# micro.net
KiCad netlist of a schematic drawn in Altium Designer
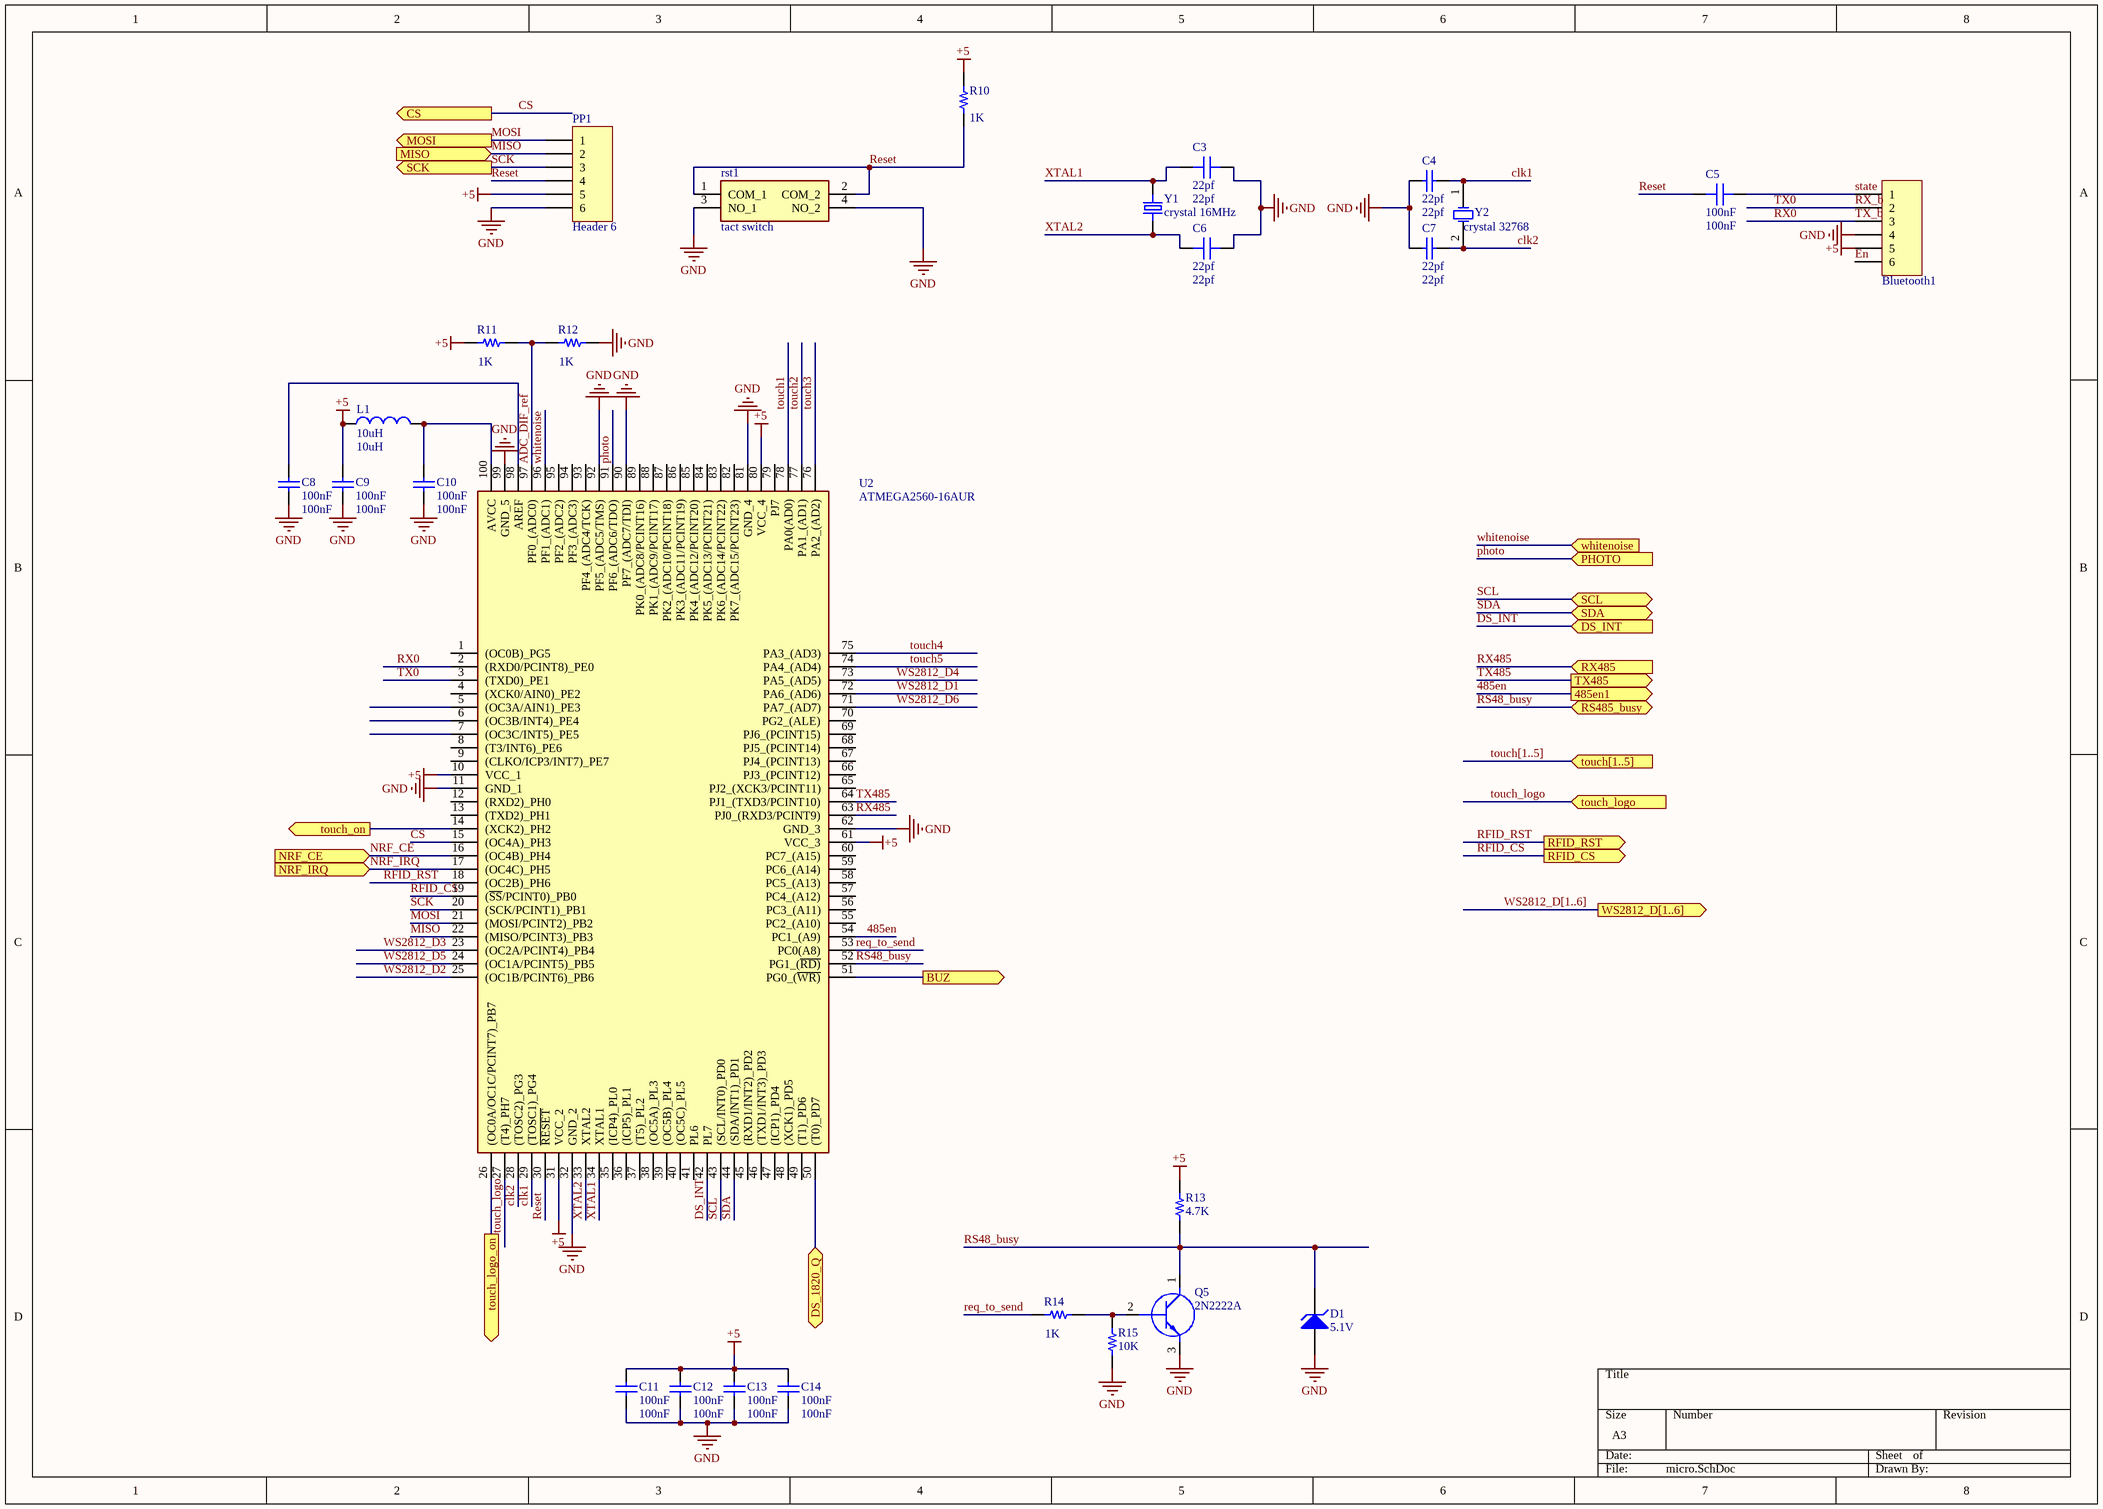
[diagram p0: micro.SchDoc]

(export (version "E")
  (design (tool "Eeschema 10.0.6"))
  (components
    (comp (ref "Bluetooth1")
      (value "Header 6")
      (footprint "H-1x6")
      (description "Header, 6-Pin , female")
      (libsource (lib "Mine-Discreet") (part "H-1x6"))
    )
    (comp (ref "C3")
      (value "22pf")
      (footprint "0603C")
      (description "CAP SMD 0603")
      (fields (field (name "PART NUMBER") "C0805X106K9RAC7800") (field (name "ALTIUM_VALUE") "22pf"))
      (libsource (lib "lamp control-ver2") (part "Capacitor"))
    )
    (comp (ref "C4")
      (value "22pf")
      (footprint "0603C")
      (description "CAP SMD 0603")
      (fields (field (name "ALTIUM_VALUE") "22pf") (field (name "PUBLISHER") "Altium Limited"))
      (libsource (lib "Miscellaneous Devices") (part "Cap"))
    )
    (comp (ref "C5")
      (value "100nF")
      (footprint "0603C")
      (description "CAP SMD 0603")
      (fields (field (name "PART NUMBER") "C0805X106K9RAC7800") (field (name "ALTIUM_VALUE") "100nF"))
      (libsource (lib "lamp control-ver2") (part "Capacitor"))
    )
    (comp (ref "C6")
      (value "22pf")
      (footprint "0603C")
      (description "CAP SMD 0603")
      (fields (field (name "PART NUMBER") "C0805X106K9RAC7800") (field (name "ALTIUM_VALUE") "22pf"))
      (libsource (lib "lamp control-ver2") (part "Capacitor"))
    )
    (comp (ref "C7")
      (value "22pf")
      (footprint "0603C")
      (description "CAP SMD 0603")
      (fields (field (name "ALTIUM_VALUE") "22pf") (field (name "PUBLISHER") "Altium Limited"))
      (libsource (lib "Miscellaneous Devices") (part "Cap"))
    )
    (comp (ref "C8")
      (value "100nF")
      (footprint "0603C")
      (description "CAP SMD 0603")
      (fields (field (name "ALTIUM_VALUE") "100nF") (field (name "PUBLISHER") "Altium Limited"))
      (libsource (lib "Miscellaneous Devices") (part "Cap"))
    )
    (comp (ref "C9")
      (value "100nF")
      (footprint "0603C")
      (description "CAP SMD 0603")
      (fields (field (name "ALTIUM_VALUE") "100nF") (field (name "PUBLISHER") "Altium Limited"))
      (libsource (lib "Miscellaneous Devices") (part "Cap"))
    )
    (comp (ref "C10")
      (value "100nF")
      (footprint "0603C")
      (description "CAP SMD 0603")
      (fields (field (name "ALTIUM_VALUE") "100nF") (field (name "PUBLISHER") "Altium Limited"))
      (libsource (lib "Miscellaneous Devices") (part "Cap"))
    )
    (comp (ref "C11")
      (value "100nF")
      (footprint "0603C")
      (description "CAP SMD 0603")
      (fields (field (name "ALTIUM_VALUE") "100nF") (field (name "PUBLISHER") "Altium Limited"))
      (libsource (lib "Miscellaneous Devices") (part "Cap"))
    )
    (comp (ref "C12")
      (value "100nF")
      (footprint "0603C")
      (description "CAP SMD 0603")
      (fields (field (name "ALTIUM_VALUE") "100nF") (field (name "PUBLISHER") "Altium Limited"))
      (libsource (lib "Miscellaneous Devices") (part "Cap"))
    )
    (comp (ref "C13")
      (value "100nF")
      (footprint "0603C")
      (description "CAP SMD 0603")
      (fields (field (name "ALTIUM_VALUE") "100nF") (field (name "PUBLISHER") "Altium Limited"))
      (libsource (lib "Miscellaneous Devices") (part "Cap"))
    )
    (comp (ref "C14")
      (value "100nF")
      (footprint "0603C")
      (description "CAP SMD 0603")
      (fields (field (name "ALTIUM_VALUE") "100nF") (field (name "PUBLISHER") "Altium Limited"))
      (libsource (lib "Miscellaneous Devices") (part "Cap"))
    )
    (comp (ref "D1")
      (value "5.1V")
      (footprint "Diode 1n4148 SMD")
      (description "Zener Diode 5.1v")
      (fields (field (name "PUBLISHER") "Altium Limited"))
      (libsource (lib "Miscellaneous Devices") (part "D Zener"))
    )
    (comp (ref "L1")
      (value "10uH")
      (footprint "IND1206")
      (description "Inductor 1206")
      (fields (field (name "ALTIUM_VALUE") "10uH") (field (name "PUBLISHER") "Altium Limited"))
      (libsource (lib "Miscellaneous Devices") (part "Inductor"))
    )
    (comp (ref "PP1")
      (value "Header 6")
      (footprint "HDR1X6")
      (description "Header, 6-Pin , female")
      (fields (field (name "PUBLISHER") "Altium Limited"))
      (libsource (lib "Miscellaneous Connectors") (part "Header 6"))
    )
    (comp (ref "Q5")
      (value "2N2222A")
      (footprint "soT95p280x130-3n")
      (description "Transistor BJT NPN SMD")
      (libsource (lib "*") (part "2N2222A"))
    )
    (comp (ref "R10")
      (value "1K")
      (footprint "0603R")
      (description "RES SMD 0603")
      (fields (field (name "PART NUMBER") "RCS0805100KFKEA"))
      (libsource (lib "lamp control-ver2") (part "Resistor"))
    )
    (comp (ref "R11")
      (value "1K")
      (footprint "0603R")
      (description "RES SMD 0603")
      (fields (field (name "PART NUMBER") "RCS0805100KFKEA"))
      (libsource (lib "lamp control-ver2") (part "Resistor"))
    )
    (comp (ref "R12")
      (value "1K")
      (footprint "0603R")
      (description "RES SMD 0603")
      (fields (field (name "PART NUMBER") "RCS0805100KFKEA"))
      (libsource (lib "lamp control-ver2") (part "Resistor"))
    )
    (comp (ref "R13")
      (value "4.7K")
      (footprint "0603R")
      (description "RES SMD 0603")
      (fields (field (name "PART NUMBER") "RCS0805100KFKEA"))
      (libsource (lib "lamp control-ver2") (part "Resistor"))
    )
    (comp (ref "R14")
      (value "1K")
      (footprint "0603R")
      (description "RES SMD 0603")
      (fields (field (name "PART NUMBER") "RCS0805100KFKEA"))
      (libsource (lib "lamp control-ver2") (part "Resistor"))
    )
    (comp (ref "R15")
      (value "10K")
      (footprint "0603R")
      (description "RES SMD 0603")
      (fields (field (name "PART NUMBER") "RCS0805100KFKEA"))
      (libsource (lib "lamp control-ver2") (part "Resistor"))
    )
    (comp (ref "rst1")
      (value "tact switch")
      (footprint "DTSM63NVB")
      (description "Push Button SMD - 4PIN")
      (fields
        (field (name "MANUFACTURER_PART_NUMBER") "DTSM-66R-V-T/R")
        (field (name "MOUSER PART NUMBER") "113-DTSM66RVTR")
      )
      (libsource (lib "*") (part "DTSM-66R-V-T_R"))
    )
    (comp (ref "U2")
      (value "ATMEGA2560-16AUR")
      (footprint "QFP50P1600X1600X120-100N")
      (description "ATMEGA2560-LQFP100")
      (fields (field (name "MOUSER PART NUMBER") "556-ATMEGA2560-16AUR"))
      (libsource (lib "*") (part "ATMEGA2560-16AUR"))
    )
    (comp (ref "Y1")
      (value "crystal 16MHz")
      (footprint "XTAL_ECS-180-S-5P-DN-TR")
      (description "Crystals 16MHz")
      (fields (field (name "MP") "ECS-180-S-5P-DN-TR") (field (name "MF") "ECS International"))
      (libsource (lib "CrystalSMD") (part "ECS-180-S-5P-DN-TR"))
    )
    (comp (ref "Y2")
      (value "crystal 32768")
      (footprint "XTAL RTC")
      (description "RTC crystal")
      (libsource (lib "My Library") (part "XTAL"))
    )
  )
  (nets
    (net (code "1") (name "+5") (class "Default")
      (node (ref "Bluetooth1") (pin "5") (pinfunction "5_5") (pintype "passive"))
      (node (ref "C11") (pin "1") (pinfunction "1_1") (pintype "passive"))
      (node (ref "C12") (pin "1") (pinfunction "1_1") (pintype "passive"))
      (node (ref "C13") (pin "1") (pinfunction "1_1") (pintype "passive"))
      (node (ref "C14") (pin "1") (pinfunction "1_1") (pintype "passive"))
      (node (ref "C9") (pin "1") (pinfunction "1_1") (pintype "passive"))
      (node (ref "L1") (pin "1") (pinfunction "1_1") (pintype "passive"))
      (node (ref "PP1") (pin "5") (pinfunction "5_5") (pintype "passive"))
      (node (ref "R10") (pin "2") (pinfunction "2_2") (pintype "passive"))
      (node (ref "R11") (pin "2") (pinfunction "2_2") (pintype "passive"))
      (node (ref "R13") (pin "1") (pinfunction "1_1") (pintype "passive"))
      (node (ref "U2") (pin "10") (pinfunction "VCC_1_10") (pintype "passive"))
      (node (ref "U2") (pin "31") (pinfunction "VCC_2_31") (pintype "passive"))
      (node (ref "U2") (pin "61") (pinfunction "VCC_3_61") (pintype "passive"))
      (node (ref "U2") (pin "80") (pinfunction "VCC_4_80") (pintype "passive"))
    )
    (net (code "2") (name "/485en") (class "Default")
      (node (ref "U2") (pin "54") (pinfunction "PC1_(A9)_54") (pintype "passive"))
    )
    (net (code "3") (name "/ADC_DIF_ref") (class "Default")
      (node (ref "R11") (pin "1") (pinfunction "1_1") (pintype "passive"))
      (node (ref "R12") (pin "2") (pinfunction "2_2") (pintype "passive"))
      (node (ref "U2") (pin "97") (pinfunction "PF0_(ADC0)_97") (pintype "passive"))
    )
    (net (code "4") (name "/BUZ") (class "Default")
      (node (ref "U2") (pin "51") (pinfunction "PG0_(~{WR)}_51") (pintype "passive"))
    )
    (net (code "5") (name "/CS") (class "Default")
      (node (ref "U2") (pin "15") (pinfunction "(OC4A)_PH3_15") (pintype "passive"))
    )
    (net (code "6") (name "/DS_1820_Q") (class "Default")
      (node (ref "U2") (pin "50") (pinfunction "(T0)_PD7_50") (pintype "passive"))
    )
    (net (code "7") (name "/DS_INT") (class "Default")
      (node (ref "U2") (pin "42") (pinfunction "PL7_42") (pintype "passive"))
    )
    (net (code "8") (name "/En") (class "Default")
      (node (ref "Bluetooth1") (pin "6") (pinfunction "6_6") (pintype "passive"))
    )
    (net (code "9") (name "/MISO") (class "Default")
      (node (ref "PP1") (pin "2") (pinfunction "2_2") (pintype "passive"))
      (node (ref "U2") (pin "22") (pinfunction "(MISO/PCINT3)_PB3_22") (pintype "passive"))
    )
    (net (code "10") (name "/MOSI") (class "Default")
      (node (ref "PP1") (pin "1") (pinfunction "1_1") (pintype "passive"))
      (node (ref "U2") (pin "21") (pinfunction "(MOSI/PCINT2)_PB2_21") (pintype "passive"))
    )
    (net (code "11") (name "/NRF_CE") (class "Default")
      (node (ref "U2") (pin "16") (pinfunction "(OC4B)_PH4_16") (pintype "passive"))
    )
    (net (code "12") (name "/NRF_IRQ") (class "Default")
      (node (ref "U2") (pin "17") (pinfunction "(OC4C)_PH5_17") (pintype "passive"))
    )
    (net (code "13") (name "/RFID_CS") (class "Default")
      (node (ref "U2") (pin "19") (pinfunction "(~{SS}/PCINT0)_PB0_19") (pintype "passive"))
    )
    (net (code "14") (name "/RFID_RST") (class "Default")
      (node (ref "U2") (pin "18") (pinfunction "(OC2B)_PH6_18") (pintype "passive"))
    )
    (net (code "15") (name "/RS48_busy") (class "Default")
      (node (ref "D1") (pin "2") (pinfunction "K_2") (pintype "passive"))
      (node (ref "Q5") (pin "1") (pinfunction "C_1") (pintype "passive"))
      (node (ref "R13") (pin "2") (pinfunction "2_2") (pintype "passive"))
      (node (ref "U2") (pin "52") (pinfunction "PG1_(~{RD)}_52") (pintype "passive"))
    )
    (net (code "16") (name "/RX0") (class "Default")
      (node (ref "Bluetooth1") (pin "3") (pinfunction "3_3") (pintype "passive"))
      (node (ref "U2") (pin "2") (pinfunction "(RXD0/PCINT8)_PE0_2") (pintype "passive"))
    )
    (net (code "17") (name "/RX485") (class "Default")
      (node (ref "U2") (pin "63") (pinfunction "PJ0_(RXD3/PCINT9)_63") (pintype "passive"))
    )
    (net (code "18") (name "/RX_b") (class "Default")
      (node (ref "Bluetooth1") (pin "2") (pinfunction "2_2") (pintype "passive"))
      (node (ref "U2") (pin "3") (pinfunction "(TXD0)_PE1_3") (pintype "passive"))
    )
    (net (code "19") (name "/Reset") (class "Default")
      (node (ref "C5") (pin "2") (pinfunction "2_2") (pintype "passive"))
      (node (ref "PP1") (pin "4") (pinfunction "4_4") (pintype "passive"))
      (node (ref "R10") (pin "1") (pinfunction "1_1") (pintype "passive"))
      (node (ref "U2") (pin "30") (pinfunction "~{RESET}_30") (pintype "passive"))
      (node (ref "rst1") (pin "1") (pinfunction "COM_1_1") (pintype "passive"))
      (node (ref "rst1") (pin "2") (pinfunction "COM_2_2") (pintype "passive"))
    )
    (net (code "20") (name "/SCK") (class "Default")
      (node (ref "PP1") (pin "3") (pinfunction "3_3") (pintype "passive"))
      (node (ref "U2") (pin "20") (pinfunction "(SCK/PCINT1)_PB1_20") (pintype "passive"))
    )
    (net (code "21") (name "/SCL") (class "Default")
      (node (ref "U2") (pin "43") (pinfunction "(SCL/INT0)_PD0_43") (pintype "passive"))
    )
    (net (code "22") (name "/SDA") (class "Default")
      (node (ref "U2") (pin "44") (pinfunction "(SDA/INT1)_PD1_44") (pintype "passive"))
    )
    (net (code "23") (name "/TX485") (class "Default")
      (node (ref "U2") (pin "64") (pinfunction "PJ1_(TXD3/PCINT10)_64") (pintype "passive"))
    )
    (net (code "24") (name "/WS2812_D1") (class "Default")
      (node (ref "U2") (pin "72") (pinfunction "PA6_(AD6)_72") (pintype "passive"))
    )
    (net (code "25") (name "/WS2812_D2") (class "Default")
      (node (ref "U2") (pin "25") (pinfunction "(OC1B/PCINT6)_PB6_25") (pintype "passive"))
    )
    (net (code "26") (name "/WS2812_D3") (class "Default")
      (node (ref "U2") (pin "23") (pinfunction "(OC2A/PCINT4)_PB4_23") (pintype "passive"))
    )
    (net (code "27") (name "/WS2812_D4") (class "Default")
      (node (ref "U2") (pin "73") (pinfunction "PA5_(AD5)_73") (pintype "passive"))
    )
    (net (code "28") (name "/WS2812_D5") (class "Default")
      (node (ref "U2") (pin "24") (pinfunction "(OC1A/PCINT5)_PB5_24") (pintype "passive"))
    )
    (net (code "29") (name "/WS2812_D6") (class "Default")
      (node (ref "U2") (pin "71") (pinfunction "PA7_(AD7)_71") (pintype "passive"))
    )
    (net (code "31") (name "/XTAL1") (class "Default")
      (node (ref "C3") (pin "2") (pinfunction "2_2") (pintype "passive"))
      (node (ref "U2") (pin "34") (pinfunction "XTAL1_34") (pintype "passive"))
      (node (ref "Y1") (pin "2") (pinfunction "2_2") (pintype "passive"))
    )
    (net (code "32") (name "/XTAL2") (class "Default")
      (node (ref "C6") (pin "2") (pinfunction "2_2") (pintype "passive"))
      (node (ref "U2") (pin "33") (pinfunction "XTAL2_33") (pintype "passive"))
      (node (ref "Y1") (pin "1") (pinfunction "1_1") (pintype "passive"))
    )
    (net (code "33") (name "/clk1") (class "Default")
      (node (ref "C4") (pin "2") (pinfunction "2_2") (pintype "passive"))
      (node (ref "U2") (pin "29") (pinfunction "(TOSC1)_PG4_29") (pintype "passive"))
      (node (ref "Y2") (pin "1") (pinfunction "OSC1_1") (pintype "passive"))
    )
    (net (code "34") (name "/clk2") (class "Default")
      (node (ref "C7") (pin "1") (pinfunction "1_1") (pintype "passive"))
      (node (ref "U2") (pin "28") (pinfunction "(TOSC2)_PG3_28") (pintype "passive"))
      (node (ref "Y2") (pin "2") (pinfunction "OSC2_2") (pintype "passive"))
    )
    (net (code "35") (name "/photo") (class "Default")
      (node (ref "U2") (pin "91") (pinfunction "PF6_(ADC6/TDO)_91") (pintype "passive"))
    )
    (net (code "36") (name "/req_to_send") (class "Default")
      (node (ref "R14") (pin "2") (pinfunction "2_2") (pintype "passive"))
      (node (ref "U2") (pin "53") (pinfunction "PC0(A8)_53") (pintype "passive"))
    )
    (net (code "37") (name "/state") (class "Default")
      (node (ref "Bluetooth1") (pin "1") (pinfunction "1_1") (pintype "passive"))
      (node (ref "C5") (pin "1") (pinfunction "1_1") (pintype "passive"))
    )
    (net (code "38") (name "/touch1") (class "Default")
      (node (ref "U2") (pin "78") (pinfunction "PA0(AD0)_78") (pintype "passive"))
    )
    (net (code "39") (name "/touch2") (class "Default")
      (node (ref "U2") (pin "77") (pinfunction "PA1_(AD1)_77") (pintype "passive"))
    )
    (net (code "40") (name "/touch3") (class "Default")
      (node (ref "U2") (pin "76") (pinfunction "PA2_(AD2)_76") (pintype "passive"))
    )
    (net (code "41") (name "/touch4") (class "Default")
      (node (ref "U2") (pin "75") (pinfunction "PA3_(AD3)_75") (pintype "passive"))
    )
    (net (code "42") (name "/touch5") (class "Default")
      (node (ref "U2") (pin "74") (pinfunction "PA4_(AD4)_74") (pintype "passive"))
    )
    (net (code "44") (name "/touch_logo") (class "Default")
      (node (ref "U2") (pin "27") (pinfunction "(T4)_PH7_27") (pintype "passive"))
    )
    (net (code "45") (name "/touch_logo_on") (class "Default")
      (node (ref "U2") (pin "26") (pinfunction "(OC0A/OC1C/PCINT7)_PB7_26") (pintype "passive"))
    )
    (net (code "46") (name "/touch_on") (class "Default")
      (node (ref "U2") (pin "14") (pinfunction "(XCK2)_PH2_14") (pintype "passive"))
    )
    (net (code "47") (name "/whitenoise") (class "Default")
      (node (ref "U2") (pin "96") (pinfunction "PF1_(ADC1)_96") (pintype "passive"))
    )
    (net (code "48") (name "GND") (class "Default")
      (node (ref "Bluetooth1") (pin "4") (pinfunction "4_4") (pintype "passive"))
      (node (ref "C10") (pin "2") (pinfunction "2_2") (pintype "passive"))
      (node (ref "C11") (pin "2") (pinfunction "2_2") (pintype "passive"))
      (node (ref "C12") (pin "2") (pinfunction "2_2") (pintype "passive"))
      (node (ref "C13") (pin "2") (pinfunction "2_2") (pintype "passive"))
      (node (ref "C14") (pin "2") (pinfunction "2_2") (pintype "passive"))
      (node (ref "C3") (pin "1") (pinfunction "1_1") (pintype "passive"))
      (node (ref "C4") (pin "1") (pinfunction "1_1") (pintype "passive"))
      (node (ref "C6") (pin "1") (pinfunction "1_1") (pintype "passive"))
      (node (ref "C7") (pin "2") (pinfunction "2_2") (pintype "passive"))
      (node (ref "C8") (pin "2") (pinfunction "2_2") (pintype "passive"))
      (node (ref "C9") (pin "2") (pinfunction "2_2") (pintype "passive"))
      (node (ref "D1") (pin "1") (pinfunction "A_1") (pintype "passive"))
      (node (ref "PP1") (pin "6") (pinfunction "6_6") (pintype "passive"))
      (node (ref "Q5") (pin "3") (pinfunction "E_3") (pintype "passive"))
      (node (ref "R12") (pin "1") (pinfunction "1_1") (pintype "passive"))
      (node (ref "R15") (pin "2") (pinfunction "2_2") (pintype "passive"))
      (node (ref "U2") (pin "11") (pinfunction "GND_1_11") (pintype "passive"))
      (node (ref "U2") (pin "32") (pinfunction "GND_2_32") (pintype "passive"))
      (node (ref "U2") (pin "62") (pinfunction "GND_3_62") (pintype "passive"))
      (node (ref "U2") (pin "81") (pinfunction "GND_4_81") (pintype "passive"))
      (node (ref "U2") (pin "90") (pinfunction "PF7_(ADC7/TDI)_90") (pintype "passive"))
      (node (ref "U2") (pin "92") (pinfunction "PF5_(ADC5/TMS)_92") (pintype "passive"))
      (node (ref "U2") (pin "99") (pinfunction "GND_5_99") (pintype "passive"))
      (node (ref "rst1") (pin "3") (pinfunction "NO_1_3") (pintype "passive"))
      (node (ref "rst1") (pin "4") (pinfunction "NO_2_4") (pintype "passive"))
    )
    (net (code "49") (name "Net-(Q5-B)") (class "Default")
      (node (ref "Q5") (pin "2") (pinfunction "B_2") (pintype "passive"))
      (node (ref "R14") (pin "1") (pinfunction "1_1") (pintype "passive"))
      (node (ref "R15") (pin "1") (pinfunction "1_1") (pintype "passive"))
    )
    (net (code "50") (name "Net-(U2-AREF)") (class "Default")
      (node (ref "C8") (pin "1") (pinfunction "1_1") (pintype "passive"))
      (node (ref "U2") (pin "98") (pinfunction "AREF_98") (pintype "passive"))
    )
    (net (code "51") (name "Net-(U2-AVCC)") (class "Default")
      (node (ref "C10") (pin "1") (pinfunction "1_1") (pintype "passive"))
      (node (ref "L1") (pin "2") (pinfunction "2_2") (pintype "passive"))
      (node (ref "U2") (pin "100") (pinfunction "AVCC_100") (pintype "passive"))
    )
    (net (code "52") (name "unconnected-(U2-(CLKO{slash}ICP3{slash}INT7)_PE7-Pad9)") (class "Default")
      (node (ref "U2") (pin "9") (pinfunction "(CLKO/ICP3/INT7)_PE7_9") (pintype "passive"))
    )
    (net (code "53") (name "unconnected-(U2-(ICP1)_PD4-Pad47)") (class "Default")
      (node (ref "U2") (pin "47") (pinfunction "(ICP1)_PD4_47") (pintype "passive"))
    )
    (net (code "54") (name "unconnected-(U2-(ICP4)_PL0-Pad35)") (class "Default")
      (node (ref "U2") (pin "35") (pinfunction "(ICP4)_PL0_35") (pintype "passive"))
    )
    (net (code "55") (name "unconnected-(U2-(ICP5)_PL1-Pad36)") (class "Default")
      (node (ref "U2") (pin "36") (pinfunction "(ICP5)_PL1_36") (pintype "passive"))
    )
    (net (code "56") (name "unconnected-(U2-(OC0B)_PG5-Pad1)") (class "Default")
      (node (ref "U2") (pin "1") (pinfunction "(OC0B)_PG5_1") (pintype "passive"))
    )
    (net (code "57") (name "unconnected-(U2-(OC3A{slash}AIN1)_PE3-Pad5)") (class "Default")
      (node (ref "U2") (pin "5") (pinfunction "(OC3A/AIN1)_PE3_5") (pintype "passive"))
    )
    (net (code "58") (name "unconnected-(U2-(OC3B{slash}INT4)_PE4-Pad6)") (class "Default")
      (node (ref "U2") (pin "6") (pinfunction "(OC3B/INT4)_PE4_6") (pintype "passive"))
    )
    (net (code "59") (name "unconnected-(U2-(OC3C{slash}INT5)_PE5-Pad7)") (class "Default")
      (node (ref "U2") (pin "7") (pinfunction "(OC3C/INT5)_PE5_7") (pintype "passive"))
    )
    (net (code "60") (name "unconnected-(U2-(OC5A)_PL3-Pad38)") (class "Default")
      (node (ref "U2") (pin "38") (pinfunction "(OC5A)_PL3_38") (pintype "passive"))
    )
    (net (code "61") (name "unconnected-(U2-(OC5B)_PL4-Pad39)") (class "Default")
      (node (ref "U2") (pin "39") (pinfunction "(OC5B)_PL4_39") (pintype "passive"))
    )
    (net (code "62") (name "unconnected-(U2-(OC5C)_PL5-Pad40)") (class "Default")
      (node (ref "U2") (pin "40") (pinfunction "(OC5C)_PL5_40") (pintype "passive"))
    )
    (net (code "63") (name "unconnected-(U2-(RXD1{slash}INT2)_PD2-Pad45)") (class "Default")
      (node (ref "U2") (pin "45") (pinfunction "(RXD1/INT2)_PD2_45") (pintype "passive"))
    )
    (net (code "64") (name "unconnected-(U2-(RXD2)_PH0-Pad12)") (class "Default")
      (node (ref "U2") (pin "12") (pinfunction "(RXD2)_PH0_12") (pintype "passive"))
    )
    (net (code "65") (name "unconnected-(U2-(T1)_PD6-Pad49)") (class "Default")
      (node (ref "U2") (pin "49") (pinfunction "(T1)_PD6_49") (pintype "passive"))
    )
    (net (code "66") (name "unconnected-(U2-(T3{slash}INT6)_PE6-Pad8)") (class "Default")
      (node (ref "U2") (pin "8") (pinfunction "(T3/INT6)_PE6_8") (pintype "passive"))
    )
    (net (code "67") (name "unconnected-(U2-(T5)_PL2-Pad37)") (class "Default")
      (node (ref "U2") (pin "37") (pinfunction "(T5)_PL2_37") (pintype "passive"))
    )
    (net (code "68") (name "unconnected-(U2-(TXD1{slash}INT3)_PD3-Pad46)") (class "Default")
      (node (ref "U2") (pin "46") (pinfunction "(TXD1/INT3)_PD3_46") (pintype "passive"))
    )
    (net (code "69") (name "unconnected-(U2-(TXD2)_PH1-Pad13)") (class "Default")
      (node (ref "U2") (pin "13") (pinfunction "(TXD2)_PH1_13") (pintype "passive"))
    )
    (net (code "70") (name "unconnected-(U2-(XCK0{slash}AIN0)_PE2-Pad4)") (class "Default")
      (node (ref "U2") (pin "4") (pinfunction "(XCK0/AIN0)_PE2_4") (pintype "passive"))
    )
    (net (code "71") (name "unconnected-(U2-(XCK1)_PD5-Pad48)") (class "Default")
      (node (ref "U2") (pin "48") (pinfunction "(XCK1)_PD5_48") (pintype "passive"))
    )
    (net (code "72") (name "unconnected-(U2-PC2_(A10)-Pad55)") (class "Default")
      (node (ref "U2") (pin "55") (pinfunction "PC2_(A10)_55") (pintype "passive"))
    )
    (net (code "73") (name "unconnected-(U2-PC3_(A11)-Pad56)") (class "Default")
      (node (ref "U2") (pin "56") (pinfunction "PC3_(A11)_56") (pintype "passive"))
    )
    (net (code "74") (name "unconnected-(U2-PC4_(A12)-Pad57)") (class "Default")
      (node (ref "U2") (pin "57") (pinfunction "PC4_(A12)_57") (pintype "passive"))
    )
    (net (code "75") (name "unconnected-(U2-PC5_(A13)-Pad58)") (class "Default")
      (node (ref "U2") (pin "58") (pinfunction "PC5_(A13)_58") (pintype "passive"))
    )
    (net (code "76") (name "unconnected-(U2-PC6_(A14)-Pad59)") (class "Default")
      (node (ref "U2") (pin "59") (pinfunction "PC6_(A14)_59") (pintype "passive"))
    )
    (net (code "77") (name "unconnected-(U2-PC7_(A15)-Pad60)") (class "Default")
      (node (ref "U2") (pin "60") (pinfunction "PC7_(A15)_60") (pintype "passive"))
    )
    (net (code "78") (name "unconnected-(U2-PF2_(ADC2)-Pad95)") (class "Default")
      (node (ref "U2") (pin "95") (pinfunction "PF2_(ADC2)_95") (pintype "passive"))
    )
    (net (code "79") (name "unconnected-(U2-PF3_(ADC3)-Pad94)") (class "Default")
      (node (ref "U2") (pin "94") (pinfunction "PF3_(ADC3)_94") (pintype "passive"))
    )
    (net (code "80") (name "unconnected-(U2-PF4_(ADC4{slash}TCK)-Pad93)") (class "Default")
      (node (ref "U2") (pin "93") (pinfunction "PF4_(ADC4/TCK)_93") (pintype "passive"))
    )
    (net (code "81") (name "unconnected-(U2-PG2_(ALE)-Pad70)") (class "Default")
      (node (ref "U2") (pin "70") (pinfunction "PG2_(ALE)_70") (pintype "passive"))
    )
    (net (code "82") (name "unconnected-(U2-PJ2_(XCK3{slash}PCINT11)-Pad65)") (class "Default")
      (node (ref "U2") (pin "65") (pinfunction "PJ2_(XCK3/PCINT11)_65") (pintype "passive"))
    )
    (net (code "83") (name "unconnected-(U2-PJ3_(PCINT12)-Pad66)") (class "Default")
      (node (ref "U2") (pin "66") (pinfunction "PJ3_(PCINT12)_66") (pintype "passive"))
    )
    (net (code "84") (name "unconnected-(U2-PJ4_(PCINT13)-Pad67)") (class "Default")
      (node (ref "U2") (pin "67") (pinfunction "PJ4_(PCINT13)_67") (pintype "passive"))
    )
    (net (code "85") (name "unconnected-(U2-PJ5_(PCINT14)-Pad68)") (class "Default")
      (node (ref "U2") (pin "68") (pinfunction "PJ5_(PCINT14)_68") (pintype "passive"))
    )
    (net (code "86") (name "unconnected-(U2-PJ6_(PCINT15)-Pad69)") (class "Default")
      (node (ref "U2") (pin "69") (pinfunction "PJ6_(PCINT15)_69") (pintype "passive"))
    )
    (net (code "87") (name "unconnected-(U2-PJ7-Pad79)") (class "Default")
      (node (ref "U2") (pin "79") (pinfunction "PJ7_79") (pintype "passive"))
    )
    (net (code "88") (name "unconnected-(U2-PK0_(ADC8{slash}PCINT16)-Pad89)") (class "Default")
      (node (ref "U2") (pin "89") (pinfunction "PK0_(ADC8/PCINT16)_89") (pintype "passive"))
    )
    (net (code "89") (name "unconnected-(U2-PK1_(ADC9{slash}PCINT17)-Pad88)") (class "Default")
      (node (ref "U2") (pin "88") (pinfunction "PK1_(ADC9/PCINT17)_88") (pintype "passive"))
    )
    (net (code "90") (name "unconnected-(U2-PK2_(ADC10{slash}PCINT18)-Pad87)") (class "Default")
      (node (ref "U2") (pin "87") (pinfunction "PK2_(ADC10/PCINT18)_87") (pintype "passive"))
    )
    (net (code "91") (name "unconnected-(U2-PK3_(ADC11{slash}PCINT19)-Pad86)") (class "Default")
      (node (ref "U2") (pin "86") (pinfunction "PK3_(ADC11/PCINT19)_86") (pintype "passive"))
    )
    (net (code "92") (name "unconnected-(U2-PK4_(ADC12{slash}PCINT20)-Pad85)") (class "Default")
      (node (ref "U2") (pin "85") (pinfunction "PK4_(ADC12/PCINT20)_85") (pintype "passive"))
    )
    (net (code "93") (name "unconnected-(U2-PK5_(ADC13{slash}PCINT21)-Pad84)") (class "Default")
      (node (ref "U2") (pin "84") (pinfunction "PK5_(ADC13/PCINT21)_84") (pintype "passive"))
    )
    (net (code "94") (name "unconnected-(U2-PK6_(ADC14{slash}PCINT22)-Pad83)") (class "Default")
      (node (ref "U2") (pin "83") (pinfunction "PK6_(ADC14/PCINT22)_83") (pintype "passive"))
    )
    (net (code "95") (name "unconnected-(U2-PK7_(ADC15{slash}PCINT23)-Pad82)") (class "Default")
      (node (ref "U2") (pin "82") (pinfunction "PK7_(ADC15/PCINT23)_82") (pintype "passive"))
    )
    (net (code "96") (name "unconnected-(U2-PL6-Pad41)") (class "Default")
      (node (ref "U2") (pin "41") (pinfunction "PL6_41") (pintype "passive"))
    )
  )
)
